# USB-C_PD.net
KiCad netlist of a schematic drawn in EAGLE
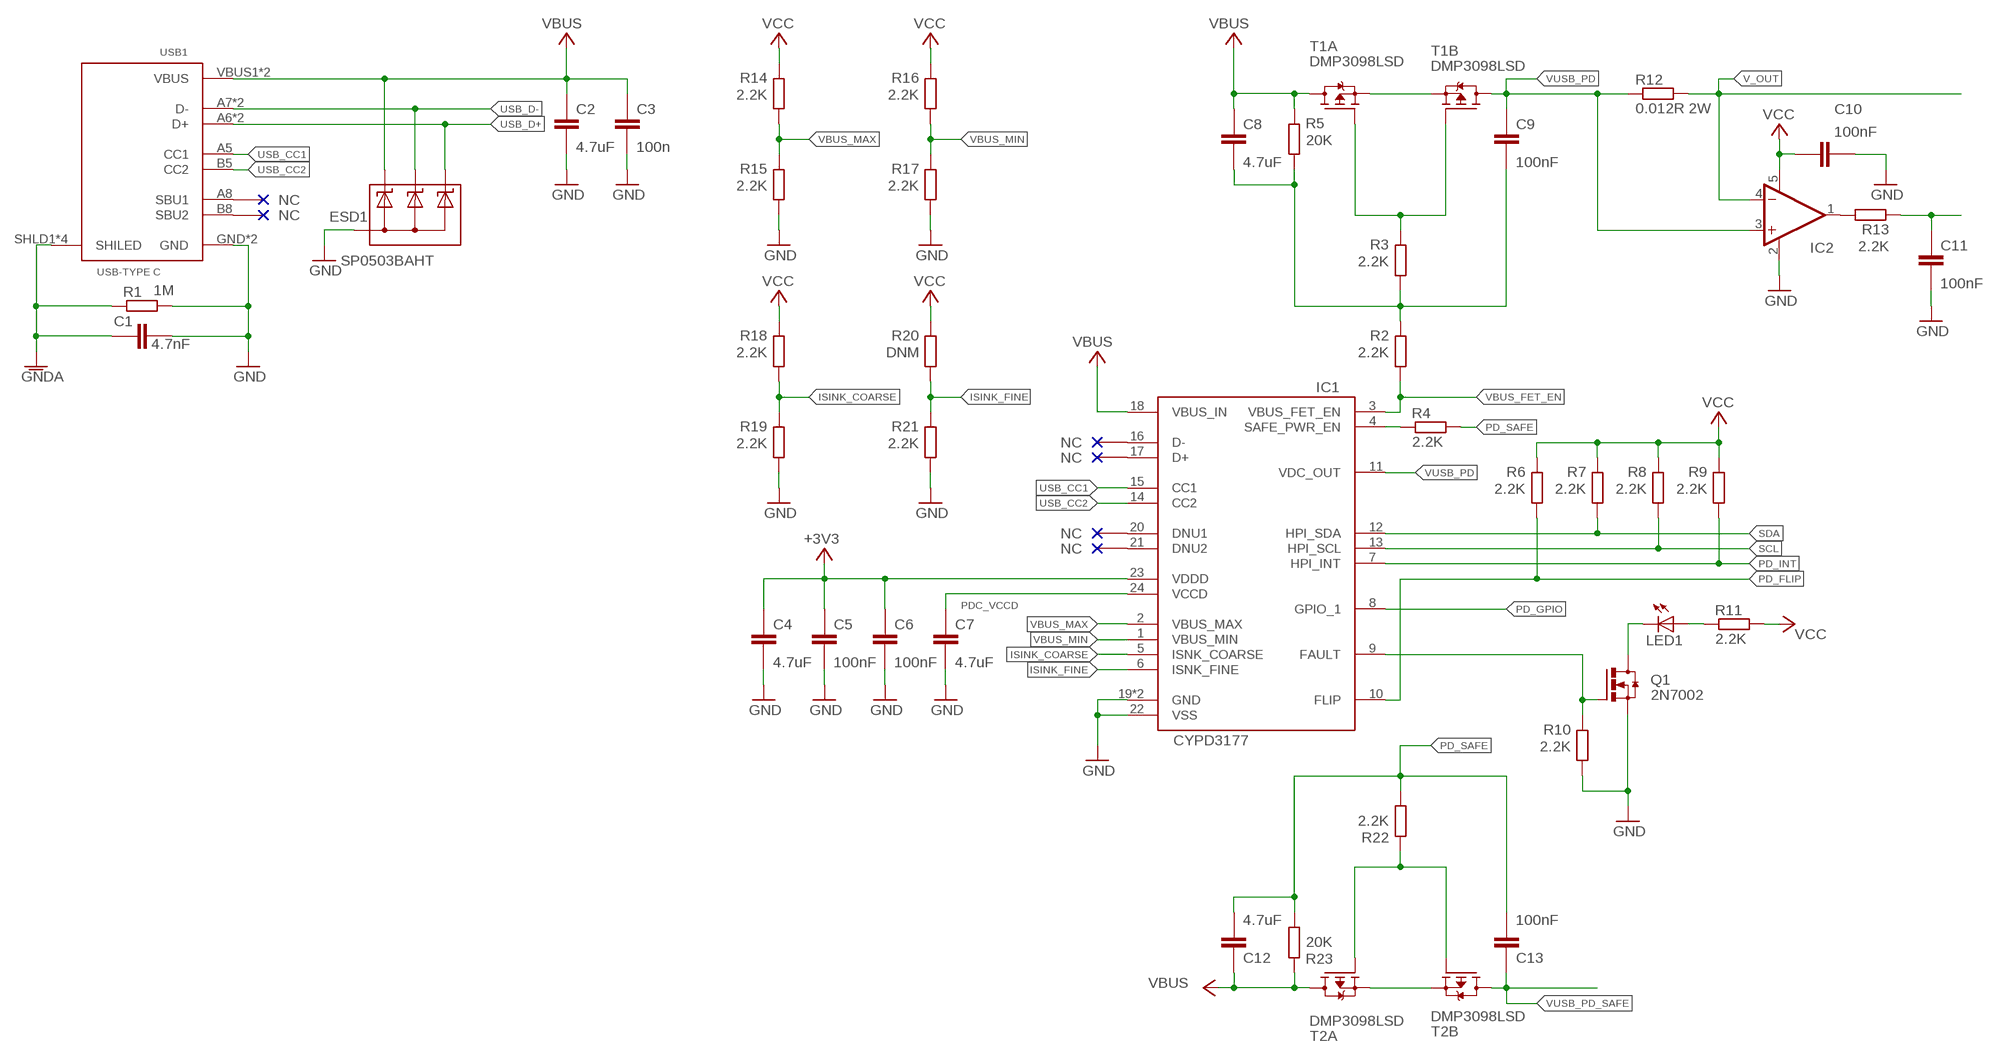
[diagram p0: schematic, sheet 1]

(export (version "E")
  (design (tool "Eeschema 10.0.6"))
  (components
    (comp (ref "C1")
      (value "4.7nF")
      (footprint "eagle-import:0402")
      (libsource (lib "eagle-import") (part "C0402"))
    )
    (comp (ref "C2")
      (value "4.7uF")
      (footprint "eagle-import:0603")
      (libsource (lib "eagle-import") (part "C0603"))
    )
    (comp (ref "C3")
      (value "100n")
      (footprint "eagle-import:0603")
      (libsource (lib "eagle-import") (part "C0603"))
    )
    (comp (ref "C4")
      (value "4.7uF")
      (footprint "eagle-import:0603")
      (libsource (lib "eagle-import") (part "C0603"))
    )
    (comp (ref "C5")
      (value "100nF")
      (footprint "eagle-import:0402")
      (libsource (lib "eagle-import") (part "C0402"))
    )
    (comp (ref "C6")
      (value "100nF")
      (footprint "eagle-import:0402")
      (libsource (lib "eagle-import") (part "C0402"))
    )
    (comp (ref "C7")
      (value "4.7uF")
      (footprint "eagle-import:0603")
      (libsource (lib "eagle-import") (part "C0603"))
    )
    (comp (ref "C8")
      (value "4.7uF")
      (footprint "eagle-import:0603")
      (libsource (lib "eagle-import") (part "C0603"))
    )
    (comp (ref "C9")
      (value "100nF")
      (footprint "eagle-import:0402")
      (libsource (lib "eagle-import") (part "C0402"))
    )
    (comp (ref "C10")
      (value "100nF")
      (footprint "eagle-import:0402")
      (libsource (lib "eagle-import") (part "C0402"))
    )
    (comp (ref "C11")
      (value "100nF")
      (footprint "eagle-import:0402")
      (libsource (lib "eagle-import") (part "C0402"))
    )
    (comp (ref "C12")
      (value "4.7uF")
      (footprint "eagle-import:0603")
      (libsource (lib "eagle-import") (part "C0603"))
    )
    (comp (ref "C13")
      (value "100nF")
      (footprint "eagle-import:0402")
      (libsource (lib "eagle-import") (part "C0402"))
    )
    (comp (ref "ESD1")
      (value "SP0503BAHT")
      (footprint "eagle-import:SOT143")
      (libsource (lib "eagle-import") (part "SP0503BAHT"))
    )
    (comp (ref "IC1")
      (value "CYPD3177-24LQXQ")
      (footprint "eagle-import:QFN50P400X400X60-25T275N")
      (libsource (lib "eagle-import") (part "CYPD3177-24LQXQ"))
    )
    (comp (ref "IC2")
      (value "INA180A3-IDBVR")
      (footprint "eagle-import:SOT23-5")
      (libsource (lib "eagle-import") (part "INA180A3-IDBVR"))
    )
    (comp (ref "LED1")
      (value "LEDCHIP-LED0805")
      (footprint "eagle-import:CHIP-LED0805")
      (libsource (lib "eagle-import") (part "LEDCHIP-LED0805"))
    )
    (comp (ref "Q1")
      (value "2N7002")
      (footprint "eagle-import:SOT23-3")
      (fields
        (field (name "DIGIKEY_PART_NUMBER") "1727-2764-1-ND")
        (field (name "MANUFACTURER") "Nexperia USA Inc.")
        (field (name "MPN") "2N7002,215")
        (field (name "CREATED_BY") "PCBLayout.com")
      )
      (libsource (lib "eagle-import") (part "2N7002,215"))
    )
    (comp (ref "R1")
      (value "1M")
      (footprint "eagle-import:0402")
      (libsource (lib "eagle-import") (part "R0402"))
    )
    (comp (ref "R2")
      (value "2.2K")
      (footprint "eagle-import:0402")
      (libsource (lib "eagle-import") (part "R0402"))
    )
    (comp (ref "R3")
      (value "2.2K")
      (footprint "eagle-import:0402")
      (libsource (lib "eagle-import") (part "R0402"))
    )
    (comp (ref "R4")
      (value "2.2K")
      (footprint "eagle-import:0402")
      (libsource (lib "eagle-import") (part "R0402"))
    )
    (comp (ref "R5")
      (value "20K")
      (footprint "eagle-import:0402")
      (libsource (lib "eagle-import") (part "R0402"))
    )
    (comp (ref "R6")
      (value "2.2K")
      (footprint "eagle-import:0402")
      (libsource (lib "eagle-import") (part "R0402"))
    )
    (comp (ref "R7")
      (value "2.2K")
      (footprint "eagle-import:0402")
      (libsource (lib "eagle-import") (part "R0402"))
    )
    (comp (ref "R8")
      (value "2.2K")
      (footprint "eagle-import:0402")
      (libsource (lib "eagle-import") (part "R0402"))
    )
    (comp (ref "R9")
      (value "2.2K")
      (footprint "eagle-import:0402")
      (libsource (lib "eagle-import") (part "R0402"))
    )
    (comp (ref "R10")
      (value "2.2K")
      (footprint "eagle-import:0402")
      (libsource (lib "eagle-import") (part "R0402"))
    )
    (comp (ref "R11")
      (value "2.2K")
      (footprint "eagle-import:0402")
      (libsource (lib "eagle-import") (part "R0402"))
    )
    (comp (ref "R12")
      (value "0.012R 2W")
      (footprint "eagle-import:R2512")
      (libsource (lib "eagle-import") (part "R-EU_R2512"))
    )
    (comp (ref "R13")
      (value "2.2K")
      (footprint "eagle-import:0402")
      (libsource (lib "eagle-import") (part "R0402"))
    )
    (comp (ref "R14")
      (value "2.2K")
      (footprint "eagle-import:0402")
      (libsource (lib "eagle-import") (part "R0402"))
    )
    (comp (ref "R15")
      (value "2.2K")
      (footprint "eagle-import:0402")
      (libsource (lib "eagle-import") (part "R0402"))
    )
    (comp (ref "R16")
      (value "2.2K")
      (footprint "eagle-import:0402")
      (libsource (lib "eagle-import") (part "R0402"))
    )
    (comp (ref "R17")
      (value "2.2K")
      (footprint "eagle-import:0402")
      (libsource (lib "eagle-import") (part "R0402"))
    )
    (comp (ref "R18")
      (value "2.2K")
      (footprint "eagle-import:0402")
      (libsource (lib "eagle-import") (part "R0402"))
    )
    (comp (ref "R19")
      (value "2.2K")
      (footprint "eagle-import:0402")
      (libsource (lib "eagle-import") (part "R0402"))
    )
    (comp (ref "R20")
      (value "DNM")
      (footprint "eagle-import:0402")
      (libsource (lib "eagle-import") (part "R0402"))
    )
    (comp (ref "R21")
      (value "2.2K")
      (footprint "eagle-import:0402")
      (libsource (lib "eagle-import") (part "R0402"))
    )
    (comp (ref "R22")
      (value "2.2K")
      (footprint "eagle-import:0402")
      (libsource (lib "eagle-import") (part "R0402"))
    )
    (comp (ref "R23")
      (value "20K")
      (footprint "eagle-import:0402")
      (libsource (lib "eagle-import") (part "R0402"))
    )
    (comp (ref "T1")
      (value "DMP3098LSD")
      (footprint "eagle-import:SO8")
      (libsource (lib "eagle-import") (part "DMP3098-LSD-13"))
    )
    (comp (ref "T2")
      (value "DMP3098LSD")
      (footprint "eagle-import:SO8")
      (libsource (lib "eagle-import") (part "DMP3098-LSD-13"))
    )
    (comp (ref "USB1")
      (value "USB_C")
      (footprint "eagle-import:USBC")
      (libsource (lib "eagle-import") (part "USB_C"))
    )
  )
  (nets
    (net (code "1") (name "+3V3") (class "Default")
      (node (ref "C4") (pin "1") (pinfunction "1_1") (pintype "passive"))
      (node (ref "C5") (pin "1") (pinfunction "1_1") (pintype "passive"))
      (node (ref "C6") (pin "1") (pinfunction "1_1") (pintype "passive"))
      (node (ref "IC1") (pin "23") (pinfunction "VDDD_23") (pintype "power_in"))
    )
    (net (code "2") (name "/PDC_VCCD") (class "Default")
      (node (ref "C7") (pin "1") (pinfunction "1_1") (pintype "passive"))
      (node (ref "IC1") (pin "24") (pinfunction "VCCD_24") (pintype "power_in"))
    )
    (net (code "3") (name "GND") (class "Default")
      (node (ref "C1") (pin "1") (pinfunction "1_1") (pintype "passive"))
      (node (ref "C10") (pin "2") (pinfunction "2_2") (pintype "passive"))
      (node (ref "C11") (pin "2") (pinfunction "2_2") (pintype "passive"))
      (node (ref "C2") (pin "2") (pinfunction "2_2") (pintype "passive"))
      (node (ref "C3") (pin "2") (pinfunction "2_2") (pintype "passive"))
      (node (ref "C4") (pin "2") (pinfunction "2_2") (pintype "passive"))
      (node (ref "C5") (pin "2") (pinfunction "2_2") (pintype "passive"))
      (node (ref "C6") (pin "2") (pinfunction "2_2") (pintype "passive"))
      (node (ref "C7") (pin "2") (pinfunction "2_2") (pintype "passive"))
      (node (ref "ESD1") (pin "1") (pinfunction "A_1") (pintype "bidirectional"))
      (node (ref "IC1") (pin "19") (pinfunction "GND_19") (pintype "power_in"))
      (node (ref "IC1") (pin "22") (pinfunction "VSS_22") (pintype "power_in"))
      (node (ref "IC1") (pin "25") (pinfunction "GND_25") (pintype "power_in"))
      (node (ref "IC2") (pin "2") (pinfunction "V-_2") (pintype "power_in"))
      (node (ref "Q1") (pin "2") (pinfunction "S_2") (pintype "passive"))
      (node (ref "R1") (pin "1") (pinfunction "1_1") (pintype "passive"))
      (node (ref "R10") (pin "1") (pinfunction "1_1") (pintype "passive"))
      (node (ref "R15") (pin "1") (pinfunction "1_1") (pintype "passive"))
      (node (ref "R17") (pin "1") (pinfunction "1_1") (pintype "passive"))
      (node (ref "R19") (pin "1") (pinfunction "1_1") (pintype "passive"))
      (node (ref "R21") (pin "1") (pinfunction "1_1") (pintype "passive"))
      (node (ref "USB1") (pin "GND") (pinfunction "GND_GND") (pintype "power_in"))
      (node (ref "USB1") (pin "GND2") (pinfunction "GND_GND2") (pintype "power_in"))
    )
    (net (code "4") (name "GNDA") (class "Default")
      (node (ref "C1") (pin "2") (pinfunction "2_2") (pintype "passive"))
      (node (ref "R1") (pin "2") (pinfunction "2_2") (pintype "passive"))
      (node (ref "USB1") (pin "SHLD1") (pinfunction "SHILED_SHLD1") (pintype "power_in"))
      (node (ref "USB1") (pin "SHLD2") (pinfunction "SHILED_SHLD2") (pintype "power_in"))
      (node (ref "USB1") (pin "SHLD5") (pinfunction "SHILED_SHLD5") (pintype "power_in"))
      (node (ref "USB1") (pin "SHLD8") (pinfunction "SHILED_SHLD8") (pintype "power_in"))
    )
    (net (code "5") (name "ISINK_COARSE") (class "Default")
      (node (ref "IC1") (pin "5") (pinfunction "ISNK_COARSE_5") (pintype "bidirectional"))
      (node (ref "R18") (pin "1") (pinfunction "1_1") (pintype "passive"))
      (node (ref "R19") (pin "2") (pinfunction "2_2") (pintype "passive"))
    )
    (net (code "6") (name "ISINK_FINE") (class "Default")
      (node (ref "IC1") (pin "6") (pinfunction "ISNK_FINE_6") (pintype "bidirectional"))
      (node (ref "R20") (pin "1") (pinfunction "1_1") (pintype "passive"))
      (node (ref "R21") (pin "2") (pinfunction "2_2") (pintype "passive"))
    )
    (net (code "7") (name "Net-(C8-Pad2)") (class "Default")
      (node (ref "C8") (pin "2") (pinfunction "2_2") (pintype "passive"))
      (node (ref "C9") (pin "2") (pinfunction "2_2") (pintype "passive"))
      (node (ref "R2") (pin "2") (pinfunction "2_2") (pintype "passive"))
      (node (ref "R3") (pin "1") (pinfunction "1_1") (pintype "passive"))
      (node (ref "R5") (pin "1") (pinfunction "1_1") (pintype "passive"))
    )
    (net (code "8") (name "Net-(C11-Pad1)") (class "Default")
      (node (ref "C11") (pin "1") (pinfunction "1_1") (pintype "passive"))
      (node (ref "R13") (pin "1") (pinfunction "1_1") (pintype "passive"))
    )
    (net (code "9") (name "Net-(IC1-FAULT)") (class "Default")
      (node (ref "IC1") (pin "9") (pinfunction "FAULT_9") (pintype "bidirectional"))
      (node (ref "Q1") (pin "1") (pinfunction "G_1") (pintype "passive"))
      (node (ref "R10") (pin "2") (pinfunction "2_2") (pintype "passive"))
    )
    (net (code "10") (name "Net-(IC1-SAFE_PWR_EN)") (class "Default")
      (node (ref "IC1") (pin "4") (pinfunction "SAFE_PWR_EN_4") (pintype "bidirectional"))
      (node (ref "R4") (pin "1") (pinfunction "1_1") (pintype "passive"))
    )
    (net (code "11") (name "Net-(IC2-OUT)") (class "Default")
      (node (ref "IC2") (pin "1") (pinfunction "OUT_1") (pintype "output"))
      (node (ref "R13") (pin "2") (pinfunction "2_2") (pintype "passive"))
    )
    (net (code "12") (name "Net-(LED1-PadA)") (class "Default")
      (node (ref "LED1") (pin "A") (pinfunction "A_A") (pintype "passive"))
      (node (ref "R11") (pin "2") (pinfunction "2_2") (pintype "passive"))
    )
    (net (code "13") (name "Net-(Q1-D)") (class "Default")
      (node (ref "LED1") (pin "C") (pinfunction "C_C") (pintype "passive"))
      (node (ref "Q1") (pin "3") (pinfunction "D_3") (pintype "passive"))
    )
    (net (code "14") (name "Net-(T1A-G)") (class "Default")
      (node (ref "R3") (pin "2") (pinfunction "2_2") (pintype "passive"))
      (node (ref "T1") (pin "2") (pinfunction "G_2") (pintype "passive"))
      (node (ref "T1") (pin "4") (pinfunction "G_4") (pintype "passive"))
    )
    (net (code "15") (name "Net-(T1A-S)") (class "Default")
      (node (ref "T1") (pin "1") (pinfunction "S_1") (pintype "passive"))
      (node (ref "T1") (pin "3") (pinfunction "S_3") (pintype "passive"))
    )
    (net (code "16") (name "Net-(T2A-G)") (class "Default")
      (node (ref "R22") (pin "2") (pinfunction "2_2") (pintype "passive"))
      (node (ref "T2") (pin "2") (pinfunction "G_2") (pintype "passive"))
      (node (ref "T2") (pin "4") (pinfunction "G_4") (pintype "passive"))
    )
    (net (code "17") (name "Net-(T2A-S)") (class "Default")
      (node (ref "T2") (pin "1") (pinfunction "S_1") (pintype "passive"))
      (node (ref "T2") (pin "3") (pinfunction "S_3") (pintype "passive"))
    )
    (net (code "18") (name "PD_FLIP") (class "Default")
      (node (ref "IC1") (pin "10") (pinfunction "FLIP_10") (pintype "bidirectional"))
      (node (ref "R6") (pin "1") (pinfunction "1_1") (pintype "passive"))
    )
    (net (code "19") (name "PD_GPIO") (class "Default")
      (node (ref "IC1") (pin "8") (pinfunction "GPIO_1_8") (pintype "bidirectional"))
    )
    (net (code "20") (name "PD_INT") (class "Default")
      (node (ref "IC1") (pin "7") (pinfunction "HPI_INT_7") (pintype "bidirectional"))
      (node (ref "R9") (pin "1") (pinfunction "1_1") (pintype "passive"))
    )
    (net (code "21") (name "PD_SAFE") (class "Default")
      (node (ref "C12") (pin "2") (pinfunction "2_2") (pintype "passive"))
      (node (ref "C13") (pin "2") (pinfunction "2_2") (pintype "passive"))
      (node (ref "R22") (pin "1") (pinfunction "1_1") (pintype "passive"))
      (node (ref "R23") (pin "1") (pinfunction "1_1") (pintype "passive"))
      (node (ref "R4") (pin "2") (pinfunction "2_2") (pintype "passive"))
    )
    (net (code "22") (name "SCL") (class "Default")
      (node (ref "IC1") (pin "13") (pinfunction "HPI_SCL_13") (pintype "bidirectional"))
      (node (ref "R8") (pin "1") (pinfunction "1_1") (pintype "passive"))
    )
    (net (code "23") (name "SDA") (class "Default")
      (node (ref "IC1") (pin "12") (pinfunction "HPI_SDA_12") (pintype "bidirectional"))
      (node (ref "R7") (pin "1") (pinfunction "1_1") (pintype "passive"))
    )
    (net (code "24") (name "USB_CC1") (class "Default")
      (node (ref "IC1") (pin "15") (pinfunction "CC1_15") (pintype "bidirectional"))
      (node (ref "USB1") (pin "A5") (pinfunction "CC1_A5") (pintype "bidirectional"))
    )
    (net (code "25") (name "USB_CC2") (class "Default")
      (node (ref "IC1") (pin "14") (pinfunction "CC2_14") (pintype "bidirectional"))
      (node (ref "USB1") (pin "B5") (pinfunction "CC2_B5") (pintype "bidirectional"))
    )
    (net (code "26") (name "USB_D+") (class "Default")
      (node (ref "ESD1") (pin "4") (pinfunction "C3_4") (pintype "bidirectional"))
      (node (ref "USB1") (pin "A6") (pinfunction "D+_A6") (pintype "bidirectional"))
      (node (ref "USB1") (pin "B6") (pinfunction "D+_B6") (pintype "bidirectional"))
    )
    (net (code "27") (name "USB_D-") (class "Default")
      (node (ref "ESD1") (pin "3") (pinfunction "C2_3") (pintype "bidirectional"))
      (node (ref "USB1") (pin "A7") (pinfunction "D-_A7") (pintype "bidirectional"))
      (node (ref "USB1") (pin "B7") (pinfunction "D-_B7") (pintype "bidirectional"))
    )
    (net (code "28") (name "VBUS") (class "Default")
      (node (ref "C12") (pin "1") (pinfunction "1_1") (pintype "passive"))
      (node (ref "C2") (pin "1") (pinfunction "1_1") (pintype "passive"))
      (node (ref "C3") (pin "1") (pinfunction "1_1") (pintype "passive"))
      (node (ref "C8") (pin "1") (pinfunction "1_1") (pintype "passive"))
      (node (ref "ESD1") (pin "2") (pinfunction "C1_2") (pintype "bidirectional"))
      (node (ref "IC1") (pin "18") (pinfunction "VBUS_IN_18") (pintype "power_in"))
      (node (ref "R23") (pin "2") (pinfunction "2_2") (pintype "passive"))
      (node (ref "R5") (pin "2") (pinfunction "2_2") (pintype "passive"))
      (node (ref "T1") (pin "7") (pinfunction "D_7") (pintype "passive"))
      (node (ref "T1") (pin "8") (pinfunction "D_8") (pintype "passive"))
      (node (ref "T2") (pin "7") (pinfunction "D_7") (pintype "passive"))
      (node (ref "T2") (pin "8") (pinfunction "D_8") (pintype "passive"))
      (node (ref "USB1") (pin "VBUS1") (pinfunction "VBUS_VBUS1") (pintype "power_in"))
      (node (ref "USB1") (pin "VBUS2") (pinfunction "VBUS_VBUS2") (pintype "power_in"))
    )
    (net (code "29") (name "VBUS_FET_EN") (class "Default")
      (node (ref "IC1") (pin "3") (pinfunction "VBUS_FET_EN_3") (pintype "bidirectional"))
      (node (ref "R2") (pin "1") (pinfunction "1_1") (pintype "passive"))
    )
    (net (code "30") (name "VBUS_MAX") (class "Default")
      (node (ref "IC1") (pin "2") (pinfunction "VBUS_MAX_2") (pintype "bidirectional"))
      (node (ref "R14") (pin "1") (pinfunction "1_1") (pintype "passive"))
      (node (ref "R15") (pin "2") (pinfunction "2_2") (pintype "passive"))
    )
    (net (code "31") (name "VBUS_MIN") (class "Default")
      (node (ref "IC1") (pin "1") (pinfunction "VBUS_MIN_1") (pintype "bidirectional"))
      (node (ref "R16") (pin "1") (pinfunction "1_1") (pintype "passive"))
      (node (ref "R17") (pin "2") (pinfunction "2_2") (pintype "passive"))
    )
    (net (code "32") (name "VCC") (class "Default")
      (node (ref "C10") (pin "1") (pinfunction "1_1") (pintype "passive"))
      (node (ref "IC2") (pin "5") (pinfunction "V+_5") (pintype "power_in"))
      (node (ref "R11") (pin "1") (pinfunction "1_1") (pintype "passive"))
      (node (ref "R14") (pin "2") (pinfunction "2_2") (pintype "passive"))
      (node (ref "R16") (pin "2") (pinfunction "2_2") (pintype "passive"))
      (node (ref "R18") (pin "2") (pinfunction "2_2") (pintype "passive"))
      (node (ref "R20") (pin "2") (pinfunction "2_2") (pintype "passive"))
      (node (ref "R6") (pin "2") (pinfunction "2_2") (pintype "passive"))
      (node (ref "R7") (pin "2") (pinfunction "2_2") (pintype "passive"))
      (node (ref "R8") (pin "2") (pinfunction "2_2") (pintype "passive"))
      (node (ref "R9") (pin "2") (pinfunction "2_2") (pintype "passive"))
    )
    (net (code "33") (name "VUSB_PD") (class "Default")
      (node (ref "C9") (pin "1") (pinfunction "1_1") (pintype "passive"))
      (node (ref "IC1") (pin "11") (pinfunction "VDC_OUT_11") (pintype "power_in"))
      (node (ref "IC2") (pin "3") (pinfunction "+IN_3") (pintype "input"))
      (node (ref "R12") (pin "1") (pinfunction "1_1") (pintype "passive"))
      (node (ref "T1") (pin "5") (pinfunction "D_5") (pintype "passive"))
      (node (ref "T1") (pin "6") (pinfunction "D_6") (pintype "passive"))
    )
    (net (code "34") (name "VUSB_PD_SAFE") (class "Default")
      (node (ref "C13") (pin "1") (pinfunction "1_1") (pintype "passive"))
      (node (ref "T2") (pin "5") (pinfunction "D_5") (pintype "passive"))
      (node (ref "T2") (pin "6") (pinfunction "D_6") (pintype "passive"))
    )
    (net (code "35") (name "V_OUT") (class "Default")
      (node (ref "IC2") (pin "4") (pinfunction "-IN_4") (pintype "input"))
      (node (ref "R12") (pin "2") (pinfunction "2_2") (pintype "passive"))
    )
    (net (code "36") (name "unconnected-(IC1-D+-Pad17)") (class "Default")
      (node (ref "IC1") (pin "17") (pinfunction "D+_17") (pintype "bidirectional"))
    )
    (net (code "37") (name "unconnected-(IC1-D--Pad16)") (class "Default")
      (node (ref "IC1") (pin "16") (pinfunction "D-_16") (pintype "bidirectional"))
    )
    (net (code "38") (name "unconnected-(IC1-DNU1-Pad20)") (class "Default")
      (node (ref "IC1") (pin "20") (pinfunction "DNU1_20") (pintype "bidirectional"))
    )
    (net (code "39") (name "unconnected-(IC1-DNU2-Pad21)") (class "Default")
      (node (ref "IC1") (pin "21") (pinfunction "DNU2_21") (pintype "bidirectional"))
    )
    (net (code "40") (name "unconnected-(USB1-SBU1-PadA8)") (class "Default")
      (node (ref "USB1") (pin "A8") (pinfunction "SBU1_A8") (pintype "bidirectional"))
    )
    (net (code "41") (name "unconnected-(USB1-SBU2-PadB8)") (class "Default")
      (node (ref "USB1") (pin "B8") (pinfunction "SBU2_B8") (pintype "bidirectional"))
    )
  )
)
